# W504X.net
KiCad netlist of a schematic drawn in EAGLE
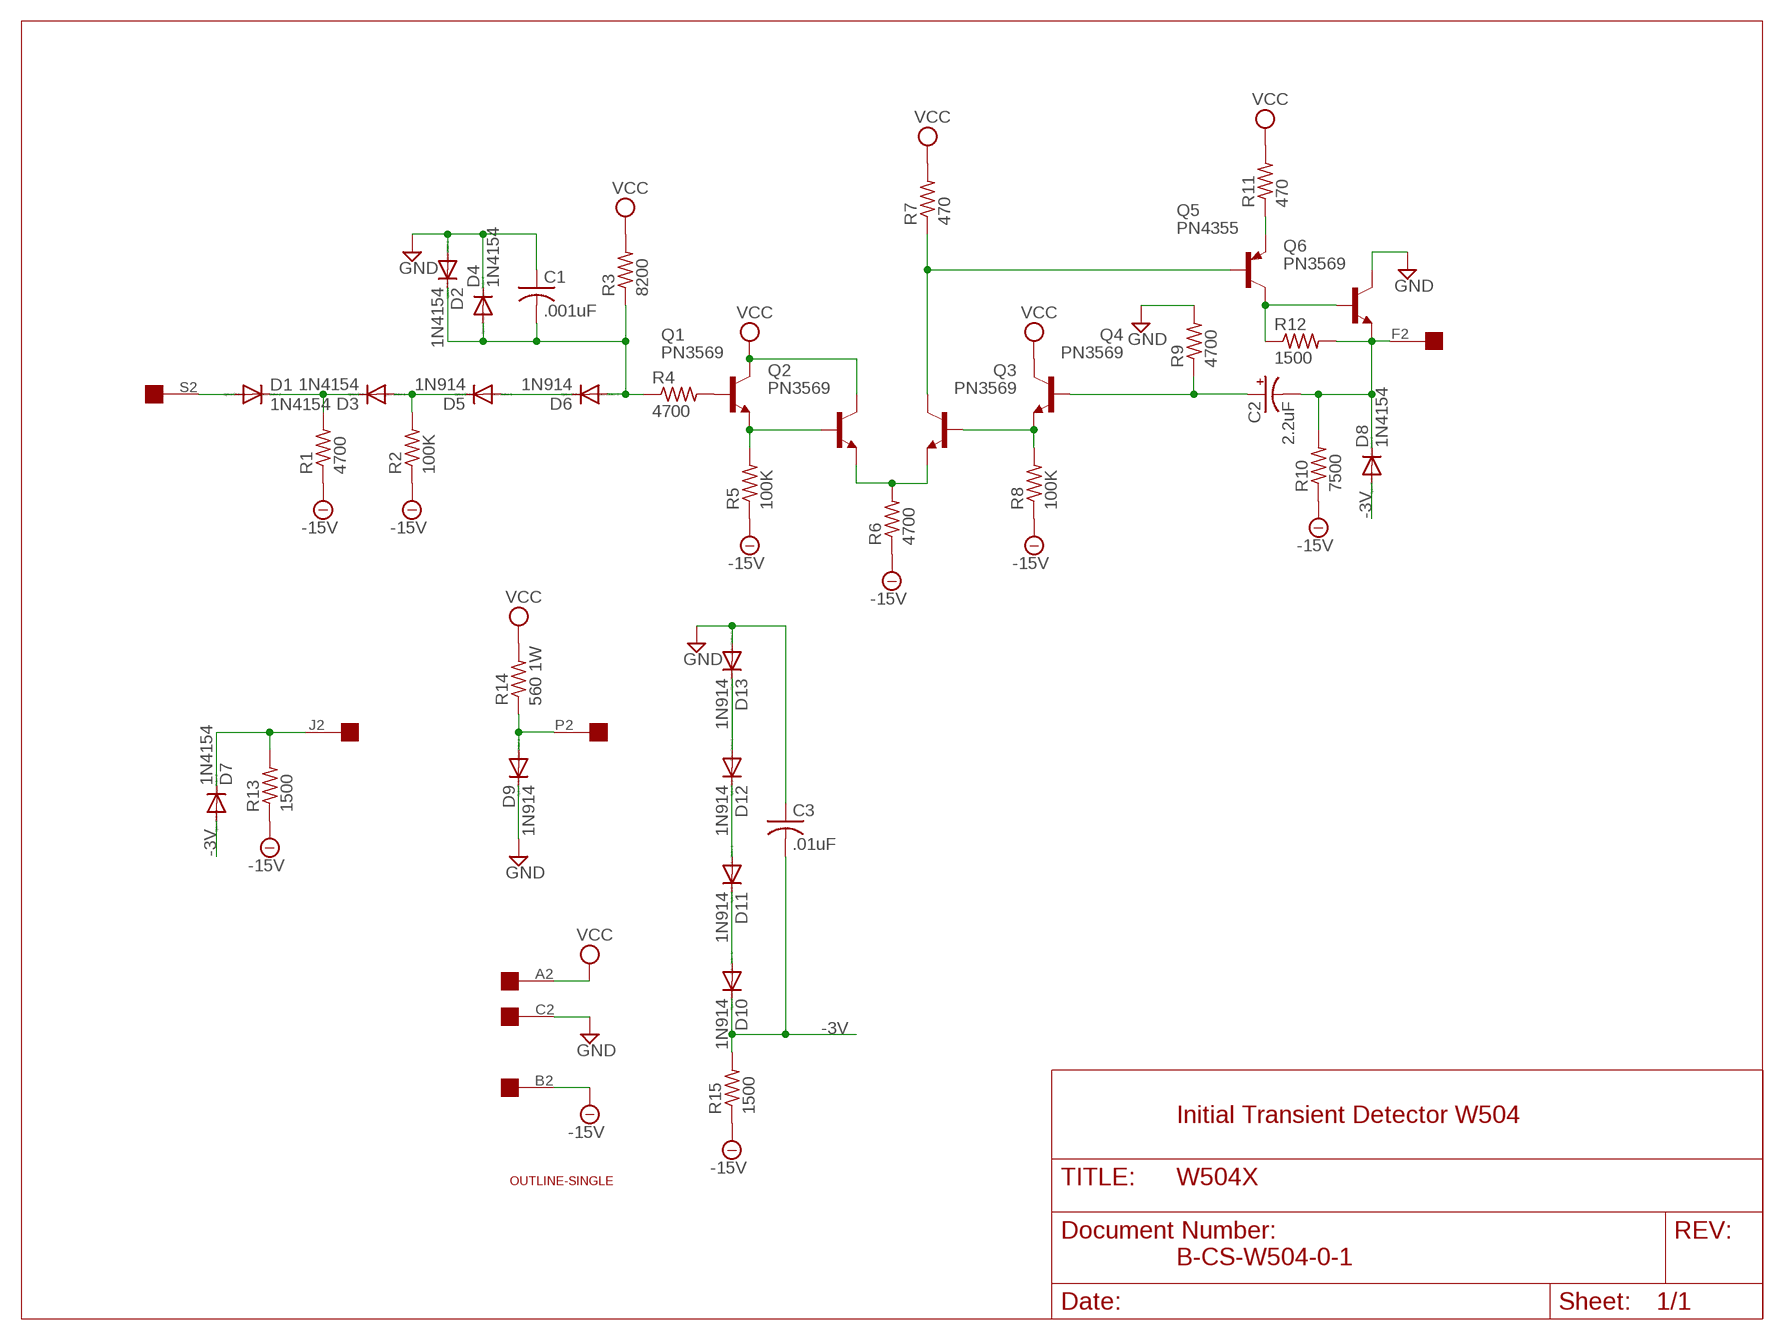
[diagram p0: schematic, sheet 1]

(export (version "E")
  (design (tool "Eeschema 10.0.6"))
  (components
    (comp (ref "C1")
      (value ".001uF")
      (footprint "eagle-import:C150-054X183")
      (libsource (lib "eagle-import") (part "C-US150-054X183"))
    )
    (comp (ref "C2")
      (value "2.2uF")
      (footprint "eagle-import:E12-4")
      (libsource (lib "eagle-import") (part "CPOL-USE12-4AXIAL"))
    )
    (comp (ref "C3")
      (value ".01uF")
      (footprint "eagle-import:C150-054X183")
      (libsource (lib "eagle-import") (part "C-US150-054X183"))
    )
    (comp (ref "D1")
      (value "1N4154")
      (footprint "eagle-import:DO35-10")
      (libsource (lib "eagle-import") (part "DIODE-DO35-10"))
    )
    (comp (ref "D2")
      (value "1N4154")
      (footprint "eagle-import:DO35-10")
      (libsource (lib "eagle-import") (part "DIODE-DO35-10"))
    )
    (comp (ref "D3")
      (value "1N4154")
      (footprint "eagle-import:DO35-10")
      (libsource (lib "eagle-import") (part "DIODE-DO35-10"))
    )
    (comp (ref "D4")
      (value "1N4154")
      (footprint "eagle-import:DO35-10")
      (libsource (lib "eagle-import") (part "DIODE-DO35-10"))
    )
    (comp (ref "D5")
      (value "1N914")
      (footprint "eagle-import:DO35-10")
      (libsource (lib "eagle-import") (part "DIODE-DO35-10"))
    )
    (comp (ref "D6")
      (value "1N914")
      (footprint "eagle-import:DO35-10")
      (libsource (lib "eagle-import") (part "DIODE-DO35-10"))
    )
    (comp (ref "D7")
      (value "1N4154")
      (footprint "eagle-import:DO35-10")
      (libsource (lib "eagle-import") (part "DIODE-DO35-10"))
    )
    (comp (ref "D8")
      (value "1N4154")
      (footprint "eagle-import:DO35-10")
      (libsource (lib "eagle-import") (part "DIODE-DO35-10"))
    )
    (comp (ref "D9")
      (value "1N914")
      (footprint "eagle-import:DO35-10")
      (libsource (lib "eagle-import") (part "DIODE-DO35-10"))
    )
    (comp (ref "D10")
      (value "1N914")
      (footprint "eagle-import:DO35-10")
      (libsource (lib "eagle-import") (part "DIODE-DO35-10"))
    )
    (comp (ref "D11")
      (value "1N914")
      (footprint "eagle-import:DO35-10")
      (libsource (lib "eagle-import") (part "DIODE-DO35-10"))
    )
    (comp (ref "D12")
      (value "1N914")
      (footprint "eagle-import:DO35-10")
      (libsource (lib "eagle-import") (part "DIODE-DO35-10"))
    )
    (comp (ref "D13")
      (value "1N914")
      (footprint "eagle-import:DO35-10")
      (libsource (lib "eagle-import") (part "DIODE-DO35-10"))
    )
    (comp (ref "Q1")
      (value "PN3569")
      (footprint "eagle-import:TO5")
      (libsource (lib "eagle-import") (part "-NPN-TO5"))
    )
    (comp (ref "Q2")
      (value "PN3569")
      (footprint "eagle-import:TO5")
      (libsource (lib "eagle-import") (part "-NPN-TO5"))
    )
    (comp (ref "Q3")
      (value "PN3569")
      (footprint "eagle-import:TO5")
      (libsource (lib "eagle-import") (part "-NPN-TO5"))
    )
    (comp (ref "Q4")
      (value "PN3569")
      (footprint "eagle-import:TO5")
      (libsource (lib "eagle-import") (part "-NPN-TO5"))
    )
    (comp (ref "Q5")
      (value "PN4355")
      (footprint "eagle-import:TO5")
      (libsource (lib "eagle-import") (part "-PNP-TO5"))
    )
    (comp (ref "Q6")
      (value "PN3569")
      (footprint "eagle-import:TO5")
      (libsource (lib "eagle-import") (part "-NPN-TO5"))
    )
    (comp (ref "R1")
      (value "4700")
      (footprint "eagle-import:0207_10")
      (libsource (lib "eagle-import") (part "R-US_0207/10"))
    )
    (comp (ref "R2")
      (value "100K")
      (footprint "eagle-import:0207_10")
      (libsource (lib "eagle-import") (part "R-US_0207/10"))
    )
    (comp (ref "R3")
      (value "8200")
      (footprint "eagle-import:0207_10")
      (libsource (lib "eagle-import") (part "R-US_0207/10"))
    )
    (comp (ref "R4")
      (value "4700")
      (footprint "eagle-import:0207_10")
      (libsource (lib "eagle-import") (part "R-US_0207/10"))
    )
    (comp (ref "R5")
      (value "100K")
      (footprint "eagle-import:0207_10")
      (libsource (lib "eagle-import") (part "R-US_0207/10"))
    )
    (comp (ref "R6")
      (value "4700")
      (footprint "eagle-import:0207_10")
      (libsource (lib "eagle-import") (part "R-US_0207/10"))
    )
    (comp (ref "R7")
      (value "470")
      (footprint "eagle-import:0207_10")
      (libsource (lib "eagle-import") (part "R-US_0207/10"))
    )
    (comp (ref "R8")
      (value "100K")
      (footprint "eagle-import:0207_10")
      (libsource (lib "eagle-import") (part "R-US_0207/10"))
    )
    (comp (ref "R9")
      (value "4700")
      (footprint "eagle-import:0207_10")
      (libsource (lib "eagle-import") (part "R-US_0207/10"))
    )
    (comp (ref "R10")
      (value "7500")
      (footprint "eagle-import:0207_10")
      (libsource (lib "eagle-import") (part "R-US_0207/10"))
    )
    (comp (ref "R11")
      (value "470")
      (footprint "eagle-import:0207_10")
      (libsource (lib "eagle-import") (part "R-US_0207/10"))
    )
    (comp (ref "R12")
      (value "1500")
      (footprint "eagle-import:0207_10")
      (libsource (lib "eagle-import") (part "R-US_0207/10"))
    )
    (comp (ref "R13")
      (value "1500")
      (footprint "eagle-import:0207_10")
      (libsource (lib "eagle-import") (part "R-US_0207/10"))
    )
    (comp (ref "R14")
      (value "560 1W")
      (footprint "eagle-import:0617_22")
      (libsource (lib "eagle-import") (part "R-US_0617/22"))
    )
    (comp (ref "R15")
      (value "1500")
      (footprint "eagle-import:0207_10")
      (libsource (lib "eagle-import") (part "R-US_0207/10"))
    )
    (comp (ref "U$1")
      (value "OUTLINE-SINGLE")
      (footprint "eagle-import:SINGLE")
      (libsource (lib "eagle-import") (part "OUTLINE-SINGLE"))
    )
    (comp (ref "U$2")
      (value "EDGE-1")
      (footprint "eagle-import:EDGE-CON1")
      (libsource (lib "eagle-import") (part "EDGE-1"))
    )
  )
  (nets
    (net (code "1") (name "-15V") (class "Default")
      (node (ref "R1") (pin "1") (pinfunction "1_1") (pintype "passive"))
      (node (ref "R10") (pin "1") (pinfunction "1_1") (pintype "passive"))
      (node (ref "R13") (pin "1") (pinfunction "1_1") (pintype "passive"))
      (node (ref "R15") (pin "1") (pinfunction "1_1") (pintype "passive"))
      (node (ref "R2") (pin "1") (pinfunction "1_1") (pintype "passive"))
      (node (ref "R5") (pin "1") (pinfunction "1_1") (pintype "passive"))
      (node (ref "R6") (pin "1") (pinfunction "1_1") (pintype "passive"))
      (node (ref "R8") (pin "1") (pinfunction "1_1") (pintype "passive"))
      (node (ref "U$2") (pin "B2") (pinfunction "1_B2") (pintype "bidirectional"))
    )
    (net (code "2") (name "/-3V") (class "Default")
      (node (ref "C3") (pin "2") (pinfunction "2_2") (pintype "passive"))
      (node (ref "D10") (pin "C") (pinfunction "C_C") (pintype "passive"))
      (node (ref "D7") (pin "A") (pinfunction "A_A") (pintype "passive"))
      (node (ref "D8") (pin "A") (pinfunction "A_A") (pintype "passive"))
      (node (ref "R15") (pin "2") (pinfunction "2_2") (pintype "passive"))
    )
    (net (code "3") (name "GND") (class "Default")
      (node (ref "C1") (pin "1") (pinfunction "1_1") (pintype "passive"))
      (node (ref "C3") (pin "1") (pinfunction "1_1") (pintype "passive"))
      (node (ref "D13") (pin "A") (pinfunction "A_A") (pintype "passive"))
      (node (ref "D2") (pin "A") (pinfunction "A_A") (pintype "passive"))
      (node (ref "D4") (pin "C") (pinfunction "C_C") (pintype "passive"))
      (node (ref "D9") (pin "C") (pinfunction "C_C") (pintype "passive"))
      (node (ref "Q6") (pin "3") (pinfunction "C_3") (pintype "passive"))
      (node (ref "R9") (pin "2") (pinfunction "2_2") (pintype "passive"))
      (node (ref "U$2") (pin "C2") (pinfunction "1_C2") (pintype "bidirectional"))
    )
    (net (code "4") (name "Net-(C1-Pad2)") (class "Default")
      (node (ref "C1") (pin "2") (pinfunction "2_2") (pintype "passive"))
      (node (ref "D2") (pin "C") (pinfunction "C_C") (pintype "passive"))
      (node (ref "D4") (pin "A") (pinfunction "A_A") (pintype "passive"))
      (node (ref "D6") (pin "A") (pinfunction "A_A") (pintype "passive"))
      (node (ref "R3") (pin "1") (pinfunction "1_1") (pintype "passive"))
      (node (ref "R4") (pin "1") (pinfunction "1_1") (pintype "passive"))
    )
    (net (code "5") (name "Net-(D1-PadC)") (class "Default")
      (node (ref "D1") (pin "C") (pinfunction "C_C") (pintype "passive"))
      (node (ref "D3") (pin "C") (pinfunction "C_C") (pintype "passive"))
      (node (ref "R1") (pin "2") (pinfunction "2_2") (pintype "passive"))
    )
    (net (code "6") (name "Net-(D3-PadA)") (class "Default")
      (node (ref "D3") (pin "A") (pinfunction "A_A") (pintype "passive"))
      (node (ref "D5") (pin "C") (pinfunction "C_C") (pintype "passive"))
      (node (ref "R2") (pin "2") (pinfunction "2_2") (pintype "passive"))
    )
    (net (code "7") (name "Net-(D5-PadA)") (class "Default")
      (node (ref "D5") (pin "A") (pinfunction "A_A") (pintype "passive"))
      (node (ref "D6") (pin "C") (pinfunction "C_C") (pintype "passive"))
    )
    (net (code "8") (name "Net-(D10-PadA)") (class "Default")
      (node (ref "D10") (pin "A") (pinfunction "A_A") (pintype "passive"))
      (node (ref "D11") (pin "C") (pinfunction "C_C") (pintype "passive"))
    )
    (net (code "9") (name "Net-(D11-PadA)") (class "Default")
      (node (ref "D11") (pin "A") (pinfunction "A_A") (pintype "passive"))
      (node (ref "D12") (pin "C") (pinfunction "C_C") (pintype "passive"))
    )
    (net (code "10") (name "Net-(D12-PadA)") (class "Default")
      (node (ref "D12") (pin "A") (pinfunction "A_A") (pintype "passive"))
      (node (ref "D13") (pin "C") (pinfunction "C_C") (pintype "passive"))
    )
    (net (code "11") (name "Net-(Q1-B)") (class "Default")
      (node (ref "Q1") (pin "2") (pinfunction "B_2") (pintype "passive"))
      (node (ref "R4") (pin "2") (pinfunction "2_2") (pintype "passive"))
    )
    (net (code "12") (name "Net-(Q1-E)") (class "Default")
      (node (ref "Q1") (pin "1") (pinfunction "E_1") (pintype "passive"))
      (node (ref "Q2") (pin "2") (pinfunction "B_2") (pintype "passive"))
      (node (ref "R5") (pin "2") (pinfunction "2_2") (pintype "passive"))
    )
    (net (code "13") (name "Net-(Q2-E)") (class "Default")
      (node (ref "Q2") (pin "1") (pinfunction "E_1") (pintype "passive"))
      (node (ref "Q3") (pin "1") (pinfunction "E_1") (pintype "passive"))
      (node (ref "R6") (pin "2") (pinfunction "2_2") (pintype "passive"))
    )
    (net (code "14") (name "Net-(Q3-B)") (class "Default")
      (node (ref "Q3") (pin "2") (pinfunction "B_2") (pintype "passive"))
      (node (ref "Q4") (pin "1") (pinfunction "E_1") (pintype "passive"))
      (node (ref "R8") (pin "2") (pinfunction "2_2") (pintype "passive"))
    )
    (net (code "15") (name "Net-(Q3-C)") (class "Default")
      (node (ref "Q3") (pin "3") (pinfunction "C_3") (pintype "passive"))
      (node (ref "Q5") (pin "2") (pinfunction "B_2") (pintype "passive"))
      (node (ref "R7") (pin "1") (pinfunction "1_1") (pintype "passive"))
    )
    (net (code "16") (name "Net-(Q4-B)") (class "Default")
      (node (ref "C2") (pin "+") (pinfunction "+_+") (pintype "passive"))
      (node (ref "Q4") (pin "2") (pinfunction "B_2") (pintype "passive"))
      (node (ref "R9") (pin "1") (pinfunction "1_1") (pintype "passive"))
    )
    (net (code "17") (name "Net-(Q5-C)") (class "Default")
      (node (ref "Q5") (pin "3") (pinfunction "C_3") (pintype "passive"))
      (node (ref "Q6") (pin "2") (pinfunction "B_2") (pintype "passive"))
      (node (ref "R12") (pin "1") (pinfunction "1_1") (pintype "passive"))
    )
    (net (code "18") (name "Net-(Q5-E)") (class "Default")
      (node (ref "Q5") (pin "1") (pinfunction "E_1") (pintype "passive"))
      (node (ref "R11") (pin "1") (pinfunction "1_1") (pintype "passive"))
    )
    (net (code "19") (name "Net-(Q6-E)") (class "Default")
      (node (ref "C2") (pin "-") (pinfunction "-_-") (pintype "passive"))
      (node (ref "D8") (pin "C") (pinfunction "C_C") (pintype "passive"))
      (node (ref "Q6") (pin "1") (pinfunction "E_1") (pintype "passive"))
      (node (ref "R10") (pin "2") (pinfunction "2_2") (pintype "passive"))
      (node (ref "R12") (pin "2") (pinfunction "2_2") (pintype "passive"))
      (node (ref "U$2") (pin "F2") (pinfunction "1_F2") (pintype "bidirectional"))
    )
    (net (code "20") (name "Net-(U$2H-1)") (class "Default")
      (node (ref "D7") (pin "C") (pinfunction "C_C") (pintype "passive"))
      (node (ref "R13") (pin "2") (pinfunction "2_2") (pintype "passive"))
      (node (ref "U$2") (pin "J2") (pinfunction "1_J2") (pintype "bidirectional"))
    )
    (net (code "21") (name "Net-(U$2M-1)") (class "Default")
      (node (ref "D9") (pin "A") (pinfunction "A_A") (pintype "passive"))
      (node (ref "R14") (pin "1") (pinfunction "1_1") (pintype "passive"))
      (node (ref "U$2") (pin "P2") (pinfunction "1_P2") (pintype "bidirectional"))
    )
    (net (code "22") (name "Net-(U$2O-1)") (class "Default")
      (node (ref "D1") (pin "A") (pinfunction "A_A") (pintype "passive"))
      (node (ref "U$2") (pin "S2") (pinfunction "1_S2") (pintype "bidirectional"))
    )
    (net (code "23") (name "VCC") (class "Default")
      (node (ref "Q1") (pin "3") (pinfunction "C_3") (pintype "passive"))
      (node (ref "Q2") (pin "3") (pinfunction "C_3") (pintype "passive"))
      (node (ref "Q4") (pin "3") (pinfunction "C_3") (pintype "passive"))
      (node (ref "R11") (pin "2") (pinfunction "2_2") (pintype "passive"))
      (node (ref "R14") (pin "2") (pinfunction "2_2") (pintype "passive"))
      (node (ref "R3") (pin "2") (pinfunction "2_2") (pintype "passive"))
      (node (ref "R7") (pin "2") (pinfunction "2_2") (pintype "passive"))
      (node (ref "U$2") (pin "A2") (pinfunction "1_A2") (pintype "bidirectional"))
    )
  )
)
